# frontpanel1_1.net
KiCad netlist of a schematic drawn in EAGLE
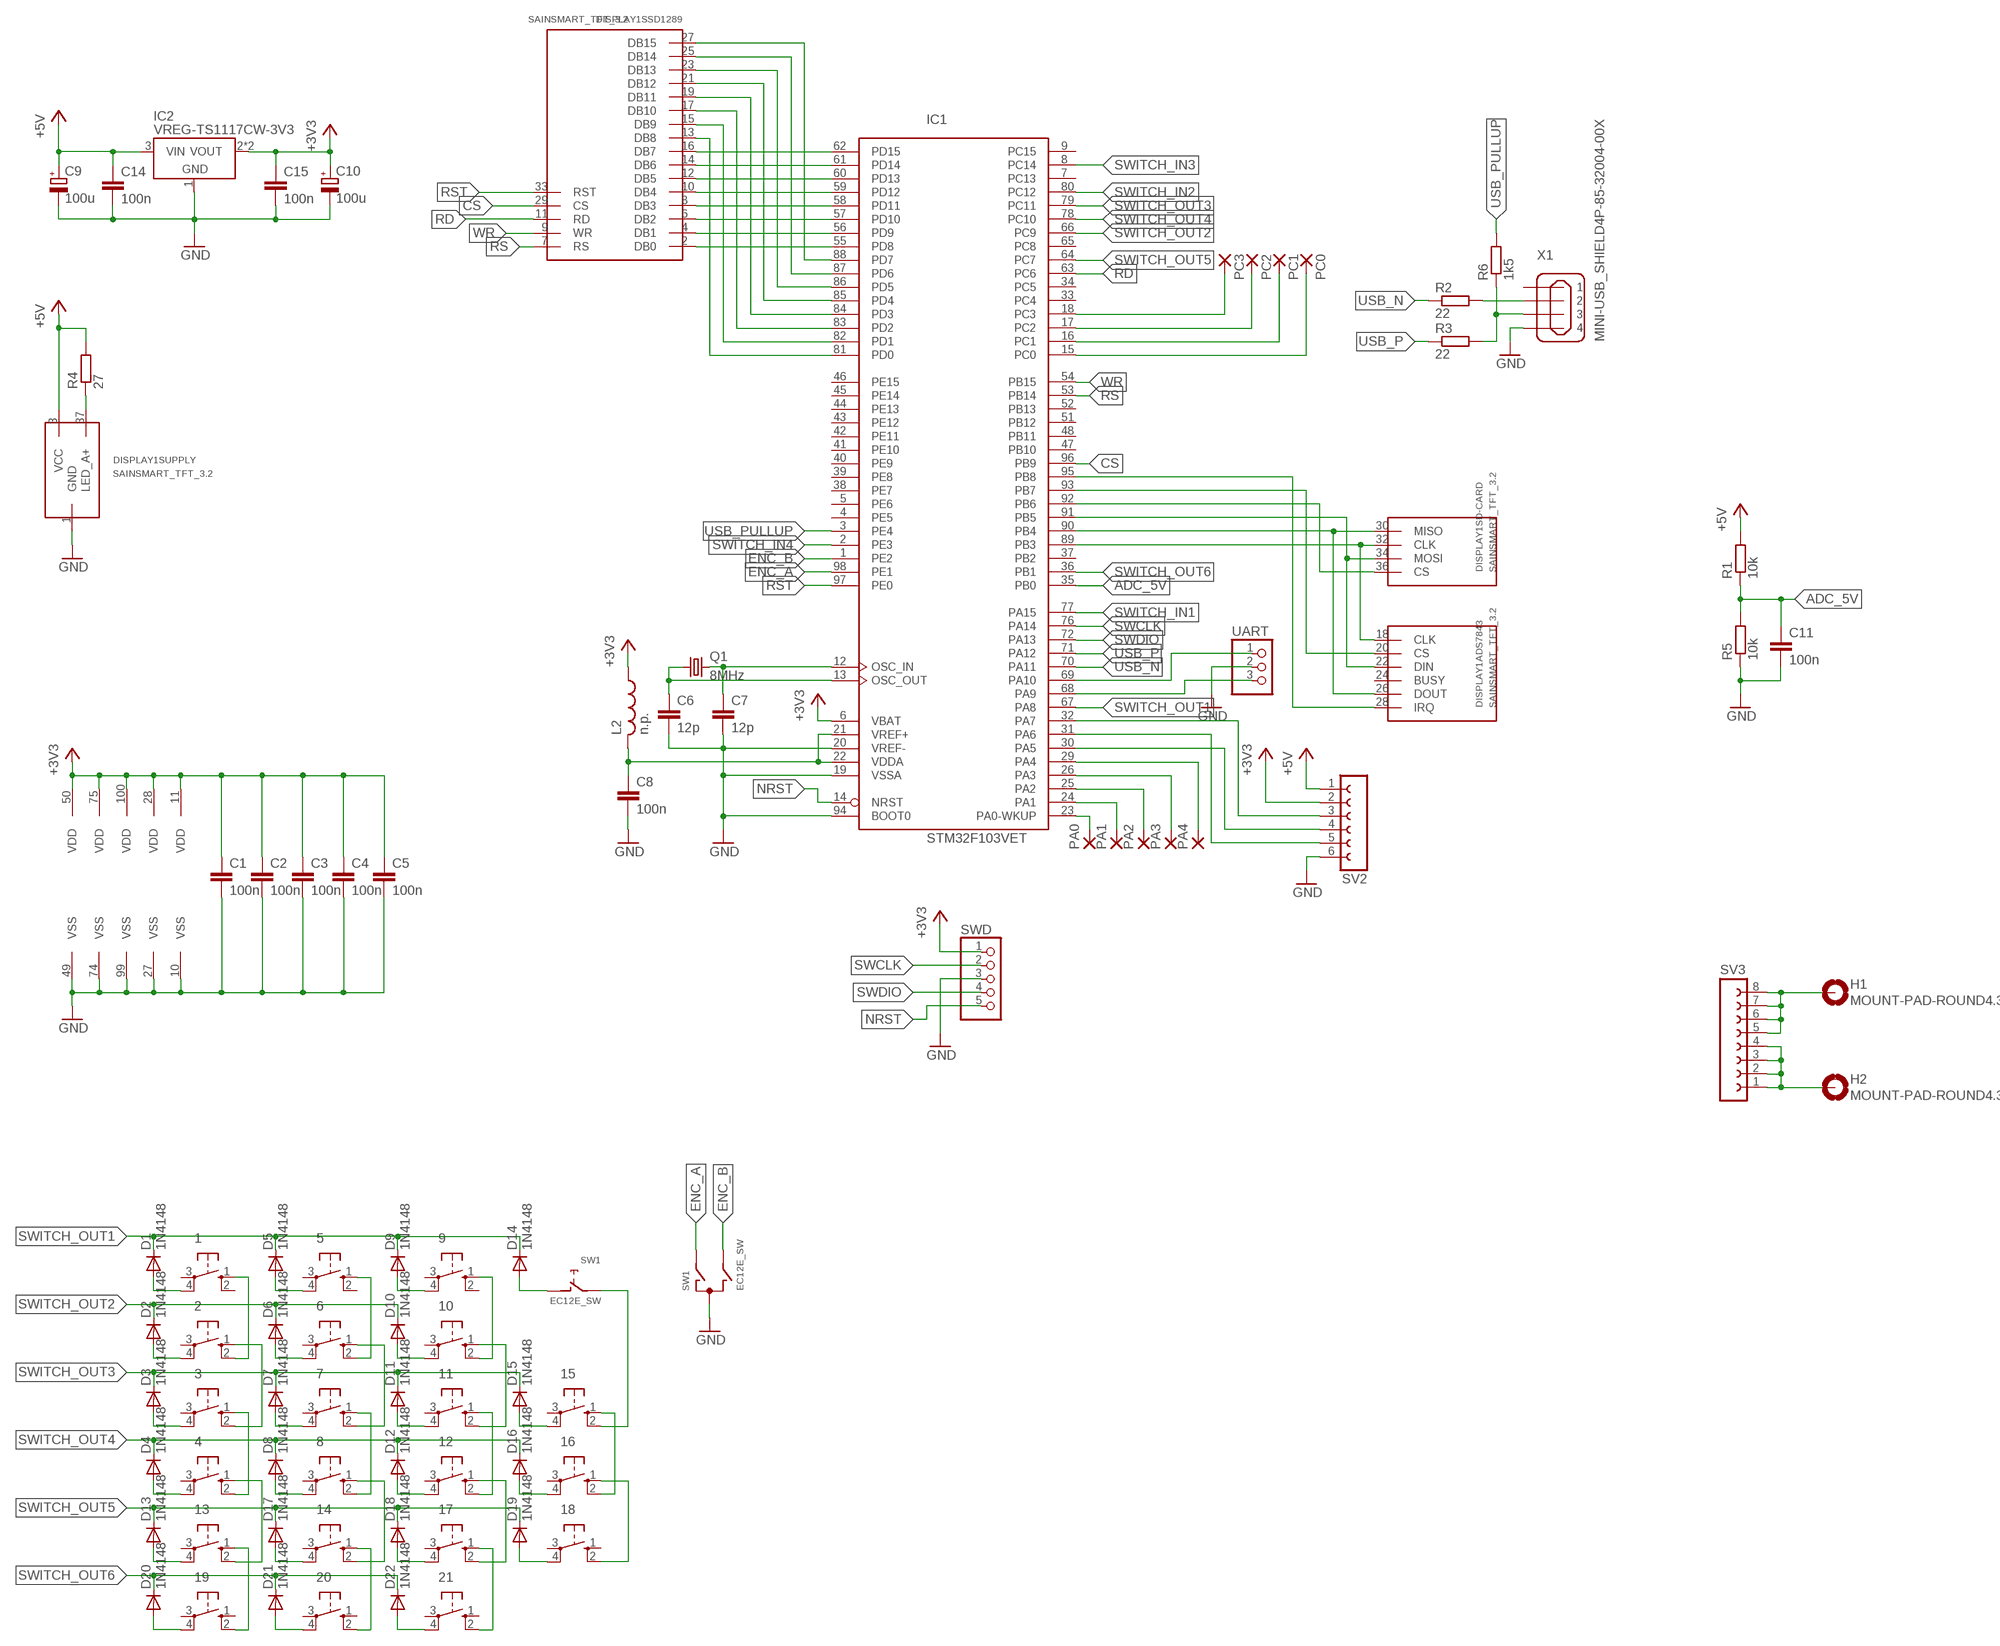
[diagram p0: schematic, sheet 1]

(export (version "E")
  (design (tool "Eeschema 10.0.6"))
  (components
    (comp (ref "1")
      (value "10-XXSMD")
      (footprint "eagle-import:SMD")
      (libsource (lib "eagle-import") (part "10-XXSMD"))
    )
    (comp (ref "2")
      (value "10-XXSMD")
      (footprint "eagle-import:SMD")
      (libsource (lib "eagle-import") (part "10-XXSMD"))
    )
    (comp (ref "3")
      (value "10-XXSMD")
      (footprint "eagle-import:SMD")
      (libsource (lib "eagle-import") (part "10-XXSMD"))
    )
    (comp (ref "4")
      (value "10-XXSMD")
      (footprint "eagle-import:SMD")
      (libsource (lib "eagle-import") (part "10-XXSMD"))
    )
    (comp (ref "5")
      (value "10-XXSMD")
      (footprint "eagle-import:SMD")
      (libsource (lib "eagle-import") (part "10-XXSMD"))
    )
    (comp (ref "6")
      (value "10-XXSMD")
      (footprint "eagle-import:SMD")
      (libsource (lib "eagle-import") (part "10-XXSMD"))
    )
    (comp (ref "7")
      (value "10-XXSMD")
      (footprint "eagle-import:SMD")
      (libsource (lib "eagle-import") (part "10-XXSMD"))
    )
    (comp (ref "8")
      (value "10-XXSMD")
      (footprint "eagle-import:SMD")
      (libsource (lib "eagle-import") (part "10-XXSMD"))
    )
    (comp (ref "9")
      (value "10-XXSMD")
      (footprint "eagle-import:SMD")
      (libsource (lib "eagle-import") (part "10-XXSMD"))
    )
    (comp (ref "10")
      (value "10-XXSMD")
      (footprint "eagle-import:SMD")
      (libsource (lib "eagle-import") (part "10-XXSMD"))
    )
    (comp (ref "11")
      (value "10-XXSMD")
      (footprint "eagle-import:SMD")
      (libsource (lib "eagle-import") (part "10-XXSMD"))
    )
    (comp (ref "12")
      (value "10-XXSMD")
      (footprint "eagle-import:SMD")
      (libsource (lib "eagle-import") (part "10-XXSMD"))
    )
    (comp (ref "13")
      (value "10-XXSMD")
      (footprint "eagle-import:SMD")
      (libsource (lib "eagle-import") (part "10-XXSMD"))
    )
    (comp (ref "14")
      (value "10-XXSMD")
      (footprint "eagle-import:SMD")
      (libsource (lib "eagle-import") (part "10-XXSMD"))
    )
    (comp (ref "15")
      (value "10-XXSMD")
      (footprint "eagle-import:SMD")
      (libsource (lib "eagle-import") (part "10-XXSMD"))
    )
    (comp (ref "16")
      (value "10-XXSMD")
      (footprint "eagle-import:SMD")
      (libsource (lib "eagle-import") (part "10-XXSMD"))
    )
    (comp (ref "17")
      (value "10-XXSMD")
      (footprint "eagle-import:SMD")
      (libsource (lib "eagle-import") (part "10-XXSMD"))
    )
    (comp (ref "18")
      (value "10-XXSMD")
      (footprint "eagle-import:SMD")
      (libsource (lib "eagle-import") (part "10-XXSMD"))
    )
    (comp (ref "19")
      (value "10-XXSMD")
      (footprint "eagle-import:SMD")
      (libsource (lib "eagle-import") (part "10-XXSMD"))
    )
    (comp (ref "20")
      (value "10-XXSMD")
      (footprint "eagle-import:SMD")
      (libsource (lib "eagle-import") (part "10-XXSMD"))
    )
    (comp (ref "21")
      (value "10-XXSMD")
      (footprint "eagle-import:SMD")
      (libsource (lib "eagle-import") (part "10-XXSMD"))
    )
    (comp (ref "C1")
      (value "100n")
      (footprint "eagle-import:C0603K")
      (libsource (lib "eagle-import") (part "C-EUC0603K"))
    )
    (comp (ref "C2")
      (value "100n")
      (footprint "eagle-import:C0603K")
      (libsource (lib "eagle-import") (part "C-EUC0603K"))
    )
    (comp (ref "C3")
      (value "100n")
      (footprint "eagle-import:C0603K")
      (libsource (lib "eagle-import") (part "C-EUC0603K"))
    )
    (comp (ref "C4")
      (value "100n")
      (footprint "eagle-import:C0603K")
      (libsource (lib "eagle-import") (part "C-EUC0603K"))
    )
    (comp (ref "C5")
      (value "100n")
      (footprint "eagle-import:C0603K")
      (libsource (lib "eagle-import") (part "C-EUC0603K"))
    )
    (comp (ref "C6")
      (value "12p")
      (footprint "eagle-import:C0603K")
      (libsource (lib "eagle-import") (part "C-EUC0603K"))
    )
    (comp (ref "C7")
      (value "12p")
      (footprint "eagle-import:C0603K")
      (libsource (lib "eagle-import") (part "C-EUC0603K"))
    )
    (comp (ref "C8")
      (value "100n")
      (footprint "eagle-import:C0603K")
      (libsource (lib "eagle-import") (part "C-EUC0603K"))
    )
    (comp (ref "C9")
      (value "100u")
      (footprint "eagle-import:153CLV-0505")
      (libsource (lib "eagle-import") (part "CPOL-EU153CLV-0505"))
    )
    (comp (ref "C10")
      (value "100u")
      (footprint "eagle-import:153CLV-0505")
      (libsource (lib "eagle-import") (part "CPOL-EU153CLV-0505"))
    )
    (comp (ref "C11")
      (value "100n")
      (footprint "eagle-import:C0603K")
      (libsource (lib "eagle-import") (part "resistormod_C-EUC0603K"))
    )
    (comp (ref "C14")
      (value "100n")
      (footprint "eagle-import:C0603K")
      (libsource (lib "eagle-import") (part "resistormod_C-EUC0603K"))
    )
    (comp (ref "C15")
      (value "100n")
      (footprint "eagle-import:C0603K")
      (libsource (lib "eagle-import") (part "resistormod_C-EUC0603K"))
    )
    (comp (ref "D1")
      (value "1N4148")
      (footprint "eagle-import:SOD323-W")
      (libsource (lib "eagle-import") (part "DIODE-SOD323-W"))
    )
    (comp (ref "D2")
      (value "1N4148")
      (footprint "eagle-import:SOD323-W")
      (libsource (lib "eagle-import") (part "DIODE-SOD323-W"))
    )
    (comp (ref "D3")
      (value "1N4148")
      (footprint "eagle-import:SOD323-W")
      (libsource (lib "eagle-import") (part "DIODE-SOD323-W"))
    )
    (comp (ref "D4")
      (value "1N4148")
      (footprint "eagle-import:SOD323-W")
      (libsource (lib "eagle-import") (part "DIODE-SOD323-W"))
    )
    (comp (ref "D5")
      (value "1N4148")
      (footprint "eagle-import:SOD323-W")
      (libsource (lib "eagle-import") (part "DIODE-SOD323-W"))
    )
    (comp (ref "D6")
      (value "1N4148")
      (footprint "eagle-import:SOD323-W")
      (libsource (lib "eagle-import") (part "DIODE-SOD323-W"))
    )
    (comp (ref "D7")
      (value "1N4148")
      (footprint "eagle-import:SOD323-W")
      (libsource (lib "eagle-import") (part "DIODE-SOD323-W"))
    )
    (comp (ref "D8")
      (value "1N4148")
      (footprint "eagle-import:SOD323-W")
      (libsource (lib "eagle-import") (part "DIODE-SOD323-W"))
    )
    (comp (ref "D9")
      (value "1N4148")
      (footprint "eagle-import:SOD323-W")
      (libsource (lib "eagle-import") (part "DIODE-SOD323-W"))
    )
    (comp (ref "D10")
      (value "1N4148")
      (footprint "eagle-import:SOD323-W")
      (libsource (lib "eagle-import") (part "DIODE-SOD323-W"))
    )
    (comp (ref "D11")
      (value "1N4148")
      (footprint "eagle-import:SOD323-W")
      (libsource (lib "eagle-import") (part "DIODE-SOD323-W"))
    )
    (comp (ref "D12")
      (value "1N4148")
      (footprint "eagle-import:SOD323-W")
      (libsource (lib "eagle-import") (part "DIODE-SOD323-W"))
    )
    (comp (ref "D13")
      (value "1N4148")
      (footprint "eagle-import:SOD323-W")
      (libsource (lib "eagle-import") (part "DIODE-SOD323-W"))
    )
    (comp (ref "D14")
      (value "1N4148")
      (footprint "eagle-import:SOD323-W")
      (libsource (lib "eagle-import") (part "DIODE-SOD323-W"))
    )
    (comp (ref "D15")
      (value "1N4148")
      (footprint "eagle-import:SOD323-W")
      (libsource (lib "eagle-import") (part "DIODE-SOD323-W"))
    )
    (comp (ref "D16")
      (value "1N4148")
      (footprint "eagle-import:SOD323-W")
      (libsource (lib "eagle-import") (part "DIODE-SOD323-W"))
    )
    (comp (ref "D17")
      (value "1N4148")
      (footprint "eagle-import:SOD323-W")
      (libsource (lib "eagle-import") (part "DIODE-SOD323-W"))
    )
    (comp (ref "D18")
      (value "1N4148")
      (footprint "eagle-import:SOD323-W")
      (libsource (lib "eagle-import") (part "DIODE-SOD323-W"))
    )
    (comp (ref "D19")
      (value "1N4148")
      (footprint "eagle-import:SOD323-W")
      (libsource (lib "eagle-import") (part "DIODE-SOD323-W"))
    )
    (comp (ref "D20")
      (value "1N4148")
      (footprint "eagle-import:SOD323-W")
      (libsource (lib "eagle-import") (part "DIODE-SOD323-W"))
    )
    (comp (ref "D21")
      (value "1N4148")
      (footprint "eagle-import:SOD323-W")
      (libsource (lib "eagle-import") (part "DIODE-SOD323-W"))
    )
    (comp (ref "D22")
      (value "1N4148")
      (footprint "eagle-import:SOD323-W")
      (libsource (lib "eagle-import") (part "DIODE-SOD323-W"))
    )
    (comp (ref "DISPLAY1")
      (value "SAINSMART_TFT_3.2")
      (footprint "eagle-import:SAINSMART_TFT_3.2")
      (libsource (lib "eagle-import") (part "SAINSMART_TFT_3.2"))
    )
    (comp (ref "H1")
      (value "MOUNT-PAD-ROUND4.3")
      (footprint "eagle-import:4,3-PAD")
      (libsource (lib "eagle-import") (part "MOUNT-PAD-ROUND4.3"))
    )
    (comp (ref "H2")
      (value "MOUNT-PAD-ROUND4.3")
      (footprint "eagle-import:4,3-PAD")
      (libsource (lib "eagle-import") (part "MOUNT-PAD-ROUND4.3"))
    )
    (comp (ref "IC1")
      (value "STM32F103VET")
      (footprint "eagle-import:LQFP100")
      (libsource (lib "eagle-import") (part "STM32F103VTE"))
    )
    (comp (ref "IC2")
      (value "VREG-TS1117CW-3V3")
      (footprint "eagle-import:SOT223")
      (libsource (lib "eagle-import") (part "VREG-TS1117CW-3V3"))
    )
    (comp (ref "L2")
      (value "n.p.")
      (footprint "eagle-import:R0603")
      (libsource (lib "eagle-import") (part "INDUCTOR0603"))
    )
    (comp (ref "PA0")
      (value "SMD2")
      (footprint "eagle-import:SMD1,27-2,54")
      (libsource (lib "eagle-import") (part "SMD2"))
    )
    (comp (ref "PA1")
      (value "SMD2")
      (footprint "eagle-import:SMD1,27-2,54")
      (libsource (lib "eagle-import") (part "SMD2"))
    )
    (comp (ref "PA2")
      (value "SMD2")
      (footprint "eagle-import:SMD1,27-2,54")
      (libsource (lib "eagle-import") (part "SMD2"))
    )
    (comp (ref "PA3")
      (value "SMD2")
      (footprint "eagle-import:SMD1,27-2,54")
      (libsource (lib "eagle-import") (part "SMD2"))
    )
    (comp (ref "PA4")
      (value "SMD2")
      (footprint "eagle-import:SMD1,27-2,54")
      (libsource (lib "eagle-import") (part "SMD2"))
    )
    (comp (ref "PC0")
      (value "SMD2")
      (footprint "eagle-import:SMD1,27-2,54")
      (libsource (lib "eagle-import") (part "SMD2"))
    )
    (comp (ref "PC1")
      (value "SMD2")
      (footprint "eagle-import:SMD1,27-2,54")
      (libsource (lib "eagle-import") (part "SMD2"))
    )
    (comp (ref "PC2")
      (value "SMD2")
      (footprint "eagle-import:SMD1,27-2,54")
      (libsource (lib "eagle-import") (part "SMD2"))
    )
    (comp (ref "PC3")
      (value "SMD2")
      (footprint "eagle-import:SMD1,27-2,54")
      (libsource (lib "eagle-import") (part "SMD2"))
    )
    (comp (ref "Q1")
      (value "8MHz")
      (footprint "eagle-import:SM49")
      (libsource (lib "eagle-import") (part "CRYSTALSM49"))
    )
    (comp (ref "R1")
      (value "10k")
      (footprint "eagle-import:R0603")
      (libsource (lib "eagle-import") (part "R-EU_R0603"))
    )
    (comp (ref "R2")
      (value "22")
      (footprint "eagle-import:R0603")
      (libsource (lib "eagle-import") (part "R-EU_R0603"))
    )
    (comp (ref "R3")
      (value "22")
      (footprint "eagle-import:R0603")
      (libsource (lib "eagle-import") (part "R-EU_R0603"))
    )
    (comp (ref "R4")
      (value "27")
      (footprint "eagle-import:R1206")
      (libsource (lib "eagle-import") (part "R-EU_R1206"))
    )
    (comp (ref "R5")
      (value "10k")
      (footprint "eagle-import:R0603")
      (libsource (lib "eagle-import") (part "R-EU_R0603"))
    )
    (comp (ref "R6")
      (value "1k5")
      (footprint "eagle-import:R0603")
      (libsource (lib "eagle-import") (part "R-EU_R0603"))
    )
    (comp (ref "SV2")
      (value "FE06-1")
      (footprint "eagle-import:FE06")
      (libsource (lib "eagle-import") (part "FE06-1"))
    )
    (comp (ref "SV3")
      (value "FE08-1")
      (footprint "eagle-import:FE08")
      (libsource (lib "eagle-import") (part "FE08-1"))
    )
    (comp (ref "SW1")
      (value "EC12E_SW")
      (footprint "eagle-import:ALPS_EC12E_SW")
      (fields (field (name "MPN") "EC12E2424407"))
      (libsource (lib "eagle-import") (part "EC12E_SW"))
    )
    (comp (ref "SWD")
      (value "PINHD-1X5")
      (footprint "eagle-import:1X05")
      (libsource (lib "eagle-import") (part "PINHD-1X5"))
    )
    (comp (ref "UART")
      (value "PINHD-1X3")
      (footprint "eagle-import:1X03")
      (libsource (lib "eagle-import") (part "PINHD-1X3"))
    )
    (comp (ref "X1")
      (value "MINI-USB_SHIELD4P-85-32004-00X")
      (footprint "eagle-import:85-32004-00X")
      (libsource (lib "eagle-import") (part "MINI-USB_SHIELD4P-85-32004-00X"))
    )
  )
  (nets
    (net (code "1") (name "+3V3") (class "Default")
      (node (ref "C1") (pin "1") (pinfunction "1_1") (pintype "passive"))
      (node (ref "C10") (pin "+") (pinfunction "+_+") (pintype "passive"))
      (node (ref "C15") (pin "1") (pinfunction "1_1") (pintype "passive"))
      (node (ref "C2") (pin "1") (pinfunction "1_1") (pintype "passive"))
      (node (ref "C3") (pin "1") (pinfunction "1_1") (pintype "passive"))
      (node (ref "C4") (pin "1") (pinfunction "1_1") (pintype "passive"))
      (node (ref "C5") (pin "1") (pinfunction "1_1") (pintype "passive"))
      (node (ref "IC1") (pin "100") (pinfunction "VDD_100") (pintype "power_in"))
      (node (ref "IC1") (pin "11") (pinfunction "VDD_11") (pintype "power_in"))
      (node (ref "IC1") (pin "28") (pinfunction "VDD_28") (pintype "power_in"))
      (node (ref "IC1") (pin "50") (pinfunction "VDD_50") (pintype "power_in"))
      (node (ref "IC1") (pin "6") (pinfunction "VBAT_6") (pintype "power_in"))
      (node (ref "IC1") (pin "75") (pinfunction "VDD_75") (pintype "power_in"))
      (node (ref "IC2") (pin "2") (pinfunction "VOUT_2") (pintype "power_in"))
      (node (ref "IC2") (pin "4") (pinfunction "VOUT_4") (pintype "power_in"))
      (node (ref "L2") (pin "1") (pinfunction "1_1") (pintype "passive"))
      (node (ref "SV2") (pin "2") (pinfunction "2_2") (pintype "passive"))
      (node (ref "SWD") (pin "1") (pinfunction "1_1") (pintype "passive"))
    )
    (net (code "2") (name "+5V") (class "Default")
      (node (ref "C14") (pin "1") (pinfunction "1_1") (pintype "passive"))
      (node (ref "C9") (pin "+") (pinfunction "+_+") (pintype "passive"))
      (node (ref "DISPLAY1") (pin "3") (pinfunction "VCC_3") (pintype "bidirectional"))
      (node (ref "IC2") (pin "3") (pinfunction "VIN_3") (pintype "power_in"))
      (node (ref "R1") (pin "2") (pinfunction "2_2") (pintype "passive"))
      (node (ref "R4") (pin "2") (pinfunction "2_2") (pintype "passive"))
      (node (ref "SV2") (pin "1") (pinfunction "1_1") (pintype "passive"))
    )
    (net (code "3") (name "ADC_5V") (class "Default")
      (node (ref "C11") (pin "1") (pinfunction "1_1") (pintype "passive"))
      (node (ref "IC1") (pin "35") (pinfunction "PB0_35") (pintype "bidirectional"))
      (node (ref "R1") (pin "1") (pinfunction "1_1") (pintype "passive"))
      (node (ref "R5") (pin "2") (pinfunction "2_2") (pintype "passive"))
    )
    (net (code "4") (name "CS") (class "Default")
      (node (ref "DISPLAY1") (pin "29") (pinfunction "CS_29") (pintype "bidirectional"))
      (node (ref "IC1") (pin "96") (pinfunction "PB9_96") (pintype "bidirectional"))
    )
    (net (code "5") (name "ENC_A") (class "Default")
      (node (ref "IC1") (pin "98") (pinfunction "PE1_98") (pintype "bidirectional"))
      (node (ref "SW1") (pin "A") (pinfunction "A_A") (pintype "passive"))
    )
    (net (code "6") (name "ENC_B") (class "Default")
      (node (ref "IC1") (pin "1") (pinfunction "PE2_1") (pintype "bidirectional"))
      (node (ref "SW1") (pin "B") (pinfunction "B_B") (pintype "passive"))
    )
    (net (code "7") (name "GND") (class "Default")
      (node (ref "C1") (pin "2") (pinfunction "2_2") (pintype "passive"))
      (node (ref "C10") (pin "-") (pinfunction "-_-") (pintype "passive"))
      (node (ref "C11") (pin "2") (pinfunction "2_2") (pintype "passive"))
      (node (ref "C14") (pin "2") (pinfunction "2_2") (pintype "passive"))
      (node (ref "C15") (pin "2") (pinfunction "2_2") (pintype "passive"))
      (node (ref "C2") (pin "2") (pinfunction "2_2") (pintype "passive"))
      (node (ref "C3") (pin "2") (pinfunction "2_2") (pintype "passive"))
      (node (ref "C4") (pin "2") (pinfunction "2_2") (pintype "passive"))
      (node (ref "C5") (pin "2") (pinfunction "2_2") (pintype "passive"))
      (node (ref "C6") (pin "2") (pinfunction "2_2") (pintype "passive"))
      (node (ref "C7") (pin "2") (pinfunction "2_2") (pintype "passive"))
      (node (ref "C8") (pin "2") (pinfunction "2_2") (pintype "passive"))
      (node (ref "C9") (pin "-") (pinfunction "-_-") (pintype "passive"))
      (node (ref "DISPLAY1") (pin "1") (pinfunction "GND_1") (pintype "bidirectional"))
      (node (ref "IC1") (pin "10") (pinfunction "VSS_10") (pintype "power_in"))
      (node (ref "IC1") (pin "19") (pinfunction "VSSA_19") (pintype "power_in"))
      (node (ref "IC1") (pin "20") (pinfunction "VREF-_20") (pintype "power_in"))
      (node (ref "IC1") (pin "27") (pinfunction "VSS_27") (pintype "power_in"))
      (node (ref "IC1") (pin "49") (pinfunction "VSS_49") (pintype "power_in"))
      (node (ref "IC1") (pin "74") (pinfunction "VSS_74") (pintype "power_in"))
      (node (ref "IC1") (pin "94") (pinfunction "BOOT0_94") (pintype "input"))
      (node (ref "IC1") (pin "99") (pinfunction "VSS_99") (pintype "power_in"))
      (node (ref "IC2") (pin "1") (pinfunction "GND_1") (pintype "power_in"))
      (node (ref "R5") (pin "1") (pinfunction "1_1") (pintype "passive"))
      (node (ref "SV2") (pin "6") (pinfunction "6_6") (pintype "passive"))
      (node (ref "SW1") (pin "C") (pinfunction "C_C") (pintype "passive"))
      (node (ref "SWD") (pin "3") (pinfunction "3_3") (pintype "passive"))
      (node (ref "UART") (pin "2") (pinfunction "2_2") (pintype "passive"))
      (node (ref "X1") (pin "4") (pinfunction "4_4") (pintype "passive"))
    )
    (net (code "8") (name "NRST") (class "Default")
      (node (ref "IC1") (pin "14") (pinfunction "NRST_14") (pintype "bidirectional"))
      (node (ref "SWD") (pin "5") (pinfunction "5_5") (pintype "passive"))
    )
    (net (code "9") (name "Net-(1-P1)") (class "Default")
      (node (ref "1") (pin "4") (pinfunction "P1_4") (pintype "passive"))
      (node (ref "D1") (pin "A") (pinfunction "A_A") (pintype "passive"))
    )
    (net (code "10") (name "Net-(1-S)") (class "Default")
      (node (ref "1") (pin "1") (pinfunction "S_1") (pintype "passive"))
      (node (ref "2") (pin "2") (pinfunction "S1_2") (pintype "passive"))
    )
    (net (code "11") (name "Net-(2-P1)") (class "Default")
      (node (ref "2") (pin "4") (pinfunction "P1_4") (pintype "passive"))
      (node (ref "D2") (pin "A") (pinfunction "A_A") (pintype "passive"))
    )
    (net (code "12") (name "Net-(2-S)") (class "Default")
      (node (ref "2") (pin "1") (pinfunction "S_1") (pintype "passive"))
      (node (ref "3") (pin "2") (pinfunction "S1_2") (pintype "passive"))
    )
    (net (code "13") (name "Net-(3-P1)") (class "Default")
      (node (ref "3") (pin "4") (pinfunction "P1_4") (pintype "passive"))
      (node (ref "D3") (pin "A") (pinfunction "A_A") (pintype "passive"))
    )
    (net (code "14") (name "Net-(4-P1)") (class "Default")
      (node (ref "4") (pin "4") (pinfunction "P1_4") (pintype "passive"))
      (node (ref "D4") (pin "A") (pinfunction "A_A") (pintype "passive"))
    )
    (net (code "15") (name "Net-(5-P1)") (class "Default")
      (node (ref "5") (pin "4") (pinfunction "P1_4") (pintype "passive"))
      (node (ref "D5") (pin "A") (pinfunction "A_A") (pintype "passive"))
    )
    (net (code "16") (name "Net-(5-S)") (class "Default")
      (node (ref "5") (pin "1") (pinfunction "S_1") (pintype "passive"))
      (node (ref "6") (pin "2") (pinfunction "S1_2") (pintype "passive"))
    )
    (net (code "17") (name "Net-(6-P1)") (class "Default")
      (node (ref "6") (pin "4") (pinfunction "P1_4") (pintype "passive"))
      (node (ref "D6") (pin "A") (pinfunction "A_A") (pintype "passive"))
    )
    (net (code "18") (name "Net-(6-S)") (class "Default")
      (node (ref "6") (pin "1") (pinfunction "S_1") (pintype "passive"))
      (node (ref "7") (pin "2") (pinfunction "S1_2") (pintype "passive"))
    )
    (net (code "19") (name "Net-(7-P1)") (class "Default")
      (node (ref "7") (pin "4") (pinfunction "P1_4") (pintype "passive"))
      (node (ref "D7") (pin "A") (pinfunction "A_A") (pintype "passive"))
    )
    (net (code "20") (name "Net-(8-P1)") (class "Default")
      (node (ref "8") (pin "4") (pinfunction "P1_4") (pintype "passive"))
      (node (ref "D8") (pin "A") (pinfunction "A_A") (pintype "passive"))
    )
    (net (code "21") (name "Net-(9-P1)") (class "Default")
      (node (ref "9") (pin "4") (pinfunction "P1_4") (pintype "passive"))
      (node (ref "D9") (pin "A") (pinfunction "A_A") (pintype "passive"))
    )
    (net (code "22") (name "Net-(10-P1)") (class "Default")
      (node (ref "10") (pin "4") (pinfunction "P1_4") (pintype "passive"))
      (node (ref "D10") (pin "A") (pinfunction "A_A") (pintype "passive"))
    )
    (net (code "23") (name "Net-(10-S)") (class "Default")
      (node (ref "10") (pin "1") (pinfunction "S_1") (pintype "passive"))
      (node (ref "11") (pin "2") (pinfunction "S1_2") (pintype "passive"))
    )
    (net (code "24") (name "Net-(10-S1)") (class "Default")
      (node (ref "10") (pin "2") (pinfunction "S1_2") (pintype "passive"))
      (node (ref "9") (pin "1") (pinfunction "S_1") (pintype "passive"))
    )
    (net (code "25") (name "Net-(11-P1)") (class "Default")
      (node (ref "11") (pin "4") (pinfunction "P1_4") (pintype "passive"))
      (node (ref "D11") (pin "A") (pinfunction "A_A") (pintype "passive"))
    )
    (net (code "26") (name "Net-(11-S)") (class "Default")
      (node (ref "11") (pin "1") (pinfunction "S_1") (pintype "passive"))
      (node (ref "12") (pin "2") (pinfunction "S1_2") (pintype "passive"))
    )
    (net (code "27") (name "Net-(12-P1)") (class "Default")
      (node (ref "12") (pin "4") (pinfunction "P1_4") (pintype "passive"))
      (node (ref "D12") (pin "A") (pinfunction "A_A") (pintype "passive"))
    )
    (net (code "28") (name "Net-(13-P1)") (class "Default")
      (node (ref "13") (pin "4") (pinfunction "P1_4") (pintype "passive"))
      (node (ref "D13") (pin "A") (pinfunction "A_A") (pintype "passive"))
    )
    (net (code "29") (name "Net-(13-S)") (class "Default")
      (node (ref "13") (pin "1") (pinfunction "S_1") (pintype "passive"))
      (node (ref "19") (pin "2") (pinfunction "S1_2") (pintype "passive"))
    )
    (net (code "30") (name "Net-(13-S1)") (class "Default")
      (node (ref "13") (pin "2") (pinfunction "S1_2") (pintype "passive"))
      (node (ref "4") (pin "1") (pinfunction "S_1") (pintype "passive"))
    )
    (net (code "31") (name "Net-(14-P1)") (class "Default")
      (node (ref "14") (pin "4") (pinfunction "P1_4") (pintype "passive"))
      (node (ref "D17") (pin "A") (pinfunction "A_A") (pintype "passive"))
    )
    (net (code "32") (name "Net-(14-S)") (class "Default")
      (node (ref "14") (pin "1") (pinfunction "S_1") (pintype "passive"))
      (node (ref "20") (pin "2") (pinfunction "S1_2") (pintype "passive"))
    )
    (net (code "33") (name "Net-(14-S1)") (class "Default")
      (node (ref "14") (pin "2") (pinfunction "S1_2") (pintype "passive"))
      (node (ref "8") (pin "1") (pinfunction "S_1") (pintype "passive"))
    )
    (net (code "34") (name "Net-(15-P1)") (class "Default")
      (node (ref "15") (pin "4") (pinfunction "P1_4") (pintype "passive"))
      (node (ref "D15") (pin "A") (pinfunction "A_A") (pintype "passive"))
    )
    (net (code "35") (name "Net-(15-S)") (class "Default")
      (node (ref "15") (pin "1") (pinfunction "S_1") (pintype "passive"))
      (node (ref "16") (pin "2") (pinfunction "S1_2") (pintype "passive"))
    )
    (net (code "36") (name "Net-(15-S1)") (class "Default")
      (node (ref "15") (pin "2") (pinfunction "S1_2") (pintype "passive"))
      (node (ref "SW1") (pin "E") (pinfunction "2_E") (pintype "passive"))
    )
    (net (code "37") (name "Net-(16-P1)") (class "Default")
      (node (ref "16") (pin "4") (pinfunction "P1_4") (pintype "passive"))
      (node (ref "D16") (pin "A") (pinfunction "A_A") (pintype "passive"))
    )
    (net (code "38") (name "Net-(17-P1)") (class "Default")
      (node (ref "17") (pin "4") (pinfunction "P1_4") (pintype "passive"))
      (node (ref "D18") (pin "A") (pinfunction "A_A") (pintype "passive"))
    )
    (net (code "39") (name "Net-(17-S)") (class "Default")
      (node (ref "17") (pin "1") (pinfunction "S_1") (pintype "passive"))
      (node (ref "21") (pin "2") (pinfunction "S1_2") (pintype "passive"))
    )
    (net (code "40") (name "Net-(18-P1)") (class "Default")
      (node (ref "18") (pin "4") (pinfunction "P1_4") (pintype "passive"))
      (node (ref "D19") (pin "A") (pinfunction "A_A") (pintype "passive"))
    )
    (net (code "41") (name "Net-(19-P1)") (class "Default")
      (node (ref "19") (pin "4") (pinfunction "P1_4") (pintype "passive"))
      (node (ref "D20") (pin "A") (pinfunction "A_A") (pintype "passive"))
    )
    (net (code "42") (name "Net-(20-P1)") (class "Default")
      (node (ref "20") (pin "4") (pinfunction "P1_4") (pintype "passive"))
      (node (ref "D21") (pin "A") (pinfunction "A_A") (pintype "passive"))
    )
    (net (code "43") (name "Net-(21-P1)") (class "Default")
      (node (ref "21") (pin "4") (pinfunction "P1_4") (pintype "passive"))
      (node (ref "D22") (pin "A") (pinfunction "A_A") (pintype "passive"))
    )
    (net (code "44") (name "Net-(DISPLAY1A-CLK)") (class "Default")
      (node (ref "DISPLAY1") (pin "18") (pinfunction "CLK_18") (pintype "bidirectional"))
      (node (ref "DISPLAY1") (pin "32") (pinfunction "CLK_32") (pintype "bidirectional"))
      (node (ref "IC1") (pin "89") (pinfunction "PB3_89") (pintype "bidirectional"))
    )
    (net (code "45") (name "Net-(DISPLAY1A-CS)") (class "Default")
      (node (ref "DISPLAY1") (pin "20") (pinfunction "CS_20") (pintype "bidirectional"))
      (node (ref "IC1") (pin "93") (pinfunction "PB7_93") (pintype "bidirectional"))
    )
    (net (code "46") (name "Net-(DISPLAY1A-DIN)") (class "Default")
      (node (ref "DISPLAY1") (pin "22") (pinfunction "DIN_22") (pintype "bidirectional"))
      (node (ref "DISPLAY1") (pin "34") (pinfunction "MOSI_34") (pintype "bidirectional"))
      (node (ref "IC1") (pin "91") (pinfunction "PB5_91") (pintype "bidirectional"))
    )
    (net (code "47") (name "Net-(DISPLAY1A-DOUT)") (class "Default")
      (node (ref "DISPLAY1") (pin "26") (pinfunction "DOUT_26") (pintype "bidirectional"))
      (node (ref "DISPLAY1") (pin "30") (pinfunction "MISO_30") (pintype "bidirectional"))
      (node (ref "IC1") (pin "90") (pinfunction "PB4_90") (pintype "bidirectional"))
    )
    (net (code "48") (name "Net-(DISPLAY1A-IRQ)") (class "Default")
      (node (ref "DISPLAY1") (pin "28") (pinfunction "IRQ_28") (pintype "bidirectional"))
      (node (ref "IC1") (pin "95") (pinfunction "PB8_95") (pintype "bidirectional"))
    )
    (net (code "49") (name "Net-(DISPLAY1B-CS)") (class "Default")
      (node (ref "DISPLAY1") (pin "36") (pinfunction "CS_36") (pintype "bidirectional"))
      (node (ref "IC1") (pin "92") (pinfunction "PB6_92") (pintype "bidirectional"))
    )
    (net (code "50") (name "Net-(DISPLAY1C-DB0)") (class "Default")
      (node (ref "DISPLAY1") (pin "2") (pinfunction "DB0_2") (pintype "bidirectional"))
      (node (ref "IC1") (pin "55") (pinfunction "PD8_55") (pintype "bidirectional"))
    )
    (net (code "51") (name "Net-(DISPLAY1C-DB1)") (class "Default")
      (node (ref "DISPLAY1") (pin "4") (pinfunction "DB1_4") (pintype "bidirectional"))
      (node (ref "IC1") (pin "56") (pinfunction "PD9_56") (pintype "bidirectional"))
    )
    (net (code "52") (name "Net-(DISPLAY1C-DB2)") (class "Default")
      (node (ref "DISPLAY1") (pin "6") (pinfunction "DB2_6") (pintype "bidirectional"))
      (node (ref "IC1") (pin "57") (pinfunction "PD10_57") (pintype "bidirectional"))
    )
    (net (code "53") (name "Net-(DISPLAY1C-DB3)") (class "Default")
      (node (ref "DISPLAY1") (pin "8") (pinfunction "DB3_8") (pintype "bidirectional"))
      (node (ref "IC1") (pin "58") (pinfunction "PD11_58") (pintype "bidirectional"))
    )
    (net (code "54") (name "Net-(DISPLAY1C-DB4)") (class "Default")
      (node (ref "DISPLAY1") (pin "10") (pinfunction "DB4_10") (pintype "bidirectional"))
      (node (ref "IC1") (pin "59") (pinfunction "PD12_59") (pintype "bidirectional"))
    )
    (net (code "55") (name "Net-(DISPLAY1C-DB5)") (class "Default")
      (node (ref "DISPLAY1") (pin "12") (pinfunction "DB5_12") (pintype "bidirectional"))
      (node (ref "IC1") (pin "60") (pinfunction "PD13_60") (pintype "bidirectional"))
    )
    (net (code "56") (name "Net-(DISPLAY1C-DB6)") (class "Default")
      (node (ref "DISPLAY1") (pin "14") (pinfunction "DB6_14") (pintype "bidirectional"))
      (node (ref "IC1") (pin "61") (pinfunction "PD14_61") (pintype "bidirectional"))
    )
    (net (code "57") (name "Net-(DISPLAY1C-DB7)") (class "Default")
      (node (ref "DISPLAY1") (pin "16") (pinfunction "DB7_16") (pintype "bidirectional"))
      (node (ref "IC1") (pin "62") (pinfunction "PD15_62") (pintype "bidirectional"))
    )
    (net (code "58") (name "Net-(DISPLAY1C-DB8)") (class "Default")
      (node (ref "DISPLAY1") (pin "13") (pinfunction "DB8_13") (pintype "bidirectional"))
      (node (ref "IC1") (pin "81") (pinfunction "PD0_81") (pintype "bidirectional"))
    )
    (net (code "59") (name "Net-(DISPLAY1C-DB9)") (class "Default")
      (node (ref "DISPLAY1") (pin "15") (pinfunction "DB9_15") (pintype "bidirectional"))
      (node (ref "IC1") (pin "82") (pinfunction "PD1_82") (pintype "bidirectional"))
    )
    (net (code "60") (name "Net-(DISPLAY1C-DB10)") (class "Default")
      (node (ref "DISPLAY1") (pin "17") (pinfunction "DB10_17") (pintype "bidirectional"))
      (node (ref "IC1") (pin "83") (pinfunction "PD2_83") (pintype "bidirectional"))
    )
    (net (code "61") (name "Net-(DISPLAY1C-DB11)") (class "Default")
      (node (ref "DISPLAY1") (pin "19") (pinfunction "DB11_19") (pintype "bidirectional"))
      (node (ref "IC1") (pin "84") (pinfunction "PD3_84") (pintype "bidirectional"))
    )
    (net (code "62") (name "Net-(DISPLAY1C-DB12)") (class "Default")
      (node (ref "DISPLAY1") (pin "21") (pinfunction "DB12_21") (pintype "bidirectional"))
      (node (ref "IC1") (pin "85") (pinfunction "PD4_85") (pintype "bidirectional"))
    )
    (net (code "63") (name "Net-(DISPLAY1C-DB13)") (class "Default")
      (node (ref "DISPLAY1") (pin "23") (pinfunction "DB13_23") (pintype "bidirectional"))
      (node (ref "IC1") (pin "86") (pinfunction "PD5_86") (pintype "bidirectional"))
    )
    (net (code "64") (name "Net-(DISPLAY1C-DB14)") (class "Default")
      (node (ref "DISPLAY1") (pin "25") (pinfunction "DB14_25") (pintype "bidirectional"))
      (node (ref "IC1") (pin "87") (pinfunction "PD6_87") (pintype "bidirectional"))
    )
    (net (code "65") (name "Net-(DISPLAY1C-DB15)") (class "Default")
      (node (ref "DISPLAY1") (pin "27") (pinfunction "DB15_27") (pintype "bidirectional"))
      (node (ref "IC1") (pin "88") (pinfunction "PD7_88") (pintype "bidirectional"))
    )
    (net (code "66") (name "Net-(DISPLAY1D-LED_A+)") (class "Default")
      (node (ref "DISPLAY1") (pin "37") (pinfunction "LED_A+_37") (pintype "bidirectional"))
      (node (ref "R4") (pin "1") (pinfunction "1_1") (pintype "passive"))
    )
    (net (code "67") (name "Net-(H1-MOUNT)") (class "Default")
      (node (ref "H1") (pin "B4,3") (pinfunction "MOUNT_B4,3") (pintype "passive"))
      (node (ref "SV3") (pin "5") (pinfunction "5_5") (pintype "passive"))
      (node (ref "SV3") (pin "6") (pinfunction "6_6") (pintype "passive"))
      (node (ref "SV3") (pin "7") (pinfunction "7_7") (pintype "passive"))
      (node (ref "SV3") (pin "8") (pinfunction "8_8") (pintype "passive"))
    )
    (net (code "68") (name "Net-(H2-MOUNT)") (class "Default")
      (node (ref "H2") (pin "B4,3") (pinfunction "MOUNT_B4,3") (pintype "passive"))
      (node (ref "SV3") (pin "1") (pinfunction "1_1") (pintype "passive"))
      (node (ref "SV3") (pin "2") (pinfunction "2_2") (pintype "passive"))
      (node (ref "SV3") (pin "3") (pinfunction "3_3") (pintype "passive"))
      (node (ref "SV3") (pin "4") (pinfunction "4_4") (pintype "passive"))
    )
    (net (code "69") (name "Net-(IC1A-OSC_IN)") (class "Default")
      (node (ref "C7") (pin "1") (pinfunction "1_1") (pintype "passive"))
      (node (ref "IC1") (pin "12") (pinfunction "OSC_IN_12") (pintype "bidirectional"))
      (node (ref "Q1") (pin "2") (pinfunction "2_2") (pintype "passive"))
    )
    (net (code "70") (name "Net-(IC1A-OSC_OUT)") (class "Default")
      (node (ref "C6") (pin "1") (pinfunction "1_1") (pintype "passive"))
      (node (ref "IC1") (pin "13") (pinfunction "OSC_OUT_13") (pintype "bidirectional"))
      (node (ref "Q1") (pin "1") (pinfunction "1_1") (pintype "passive"))
    )
    (net (code "71") (name "Net-(IC1A-PA0-WKUP)") (class "Default")
      (node (ref "IC1") (pin "23") (pinfunction "PA0-WKUP_23") (pintype "bidirectional"))
      (node (ref "PA0") (pin "1") (pinfunction "P_1") (pintype "passive"))
    )
    (net (code "72") (name "Net-(IC1A-PA1)") (class "Default")
      (node (ref "IC1") (pin "24") (pinfunction "PA1_24") (pintype "bidirectional"))
      (node (ref "PA1") (pin "1") (pinfunction "P_1") (pintype "passive"))
    )
    (net (code "73") (name "Net-(IC1A-PA2)") (class "Default")
      (node (ref "IC1") (pin "25") (pinfunction "PA2_25") (pintype "bidirectional"))
      (node (ref "PA2") (pin "1") (pinfunction "P_1") (pintype "passive"))
    )
    (net (code "74") (name "Net-(IC1A-PA3)") (class "Default")
      (node (ref "IC1") (pin "26") (pinfunction "PA3_26") (pintype "bidirectional"))
      (node (ref "PA3") (pin "1") (pinfunction "P_1") (pintype "passive"))
    )
    (net (code "75") (name "Net-(IC1A-PA4)") (class "Default")
      (node (ref "IC1") (pin "29") (pinfunction "PA4_29") (pintype "bidirectional"))
      (node (ref "PA4") (pin "1") (pinfunction "P_1") (pintype "passive"))
    )
    (net (code "76") (name "Net-(IC1A-PA5)") (class "Default")
      (node (ref "IC1") (pin "30") (pinfunction "PA5_30") (pintype "bidirectional"))
      (node (ref "SV2") (pin "4") (pinfunction "4_4") (pintype "passive"))
    )
    (net (code "77") (name "Net-(IC1A-PA6)") (class "Default")
      (node (ref "IC1") (pin "31") (pinfunction "PA6_31") (pintype "bidirectional"))
      (node (ref "SV2") (pin "5") (pinfunction "5_5") (pintype "passive"))
    )
    (net (code "78") (name "Net-(IC1A-PA7)") (class "Default")
      (node (ref "IC1") (pin "32") (pinfunction "PA7_32") (pintype "bidirectional"))
      (node (ref "SV2") (pin "3") (pinfunction "3_3") (pintype "passive"))
    )
    (net (code "79") (name "Net-(IC1A-PA9)") (class "Default")
      (node (ref "IC1") (pin "68") (pinfunction "PA9_68") (pintype "bidirectional"))
      (node (ref "UART") (pin "3") (pinfunction "3_3") (pintype "passive"))
    )
    (net (code "80") (name "Net-(IC1A-PA10)") (class "Default")
      (node (ref "IC1") (pin "69") (pinfunction "PA10_69") (pintype "bidirectional"))
      (node (ref "UART") (pin "1") (pinfunction "1_1") (pintype "passive"))
    )
    (net (code "81") (name "Net-(IC1A-PC0)") (class "Default")
      (node (ref "IC1") (pin "15") (pinfunction "PC0_15") (pintype "bidirectional"))
      (node (ref "PC0") (pin "1") (pinfunction "P_1") (pintype "passive"))
    )
    (net (code "82") (name "Net-(IC1A-PC1)") (class "Default")
      (node (ref "IC1") (pin "16") (pinfunction "PC1_16") (pintype "bidirectional"))
      (node (ref "PC1") (pin "1") (pinfunction "P_1") (pintype "passive"))
    )
    (net (code "83") (name "Net-(IC1A-PC2)") (class "Default")
      (node (ref "IC1") (pin "17") (pinfunction "PC2_17") (pintype "bidirectional"))
      (node (ref "PC2") (pin "1") (pinfunction "P_1") (pintype "passive"))
    )
    (net (code "84") (name "Net-(IC1A-PC3)") (class "Default")
      (node (ref "IC1") (pin "18") (pinfunction "PC3_18") (pintype "bidirectional"))
      (node (ref "PC3") (pin "1") (pinfunction "P_1") (pintype "passive"))
    )
    (net (code "85") (name "Net-(IC1A-VDDA)") (class "Default")
      (node (ref "C8") (pin "1") (pinfunction "1_1") (pintype "passive"))
      (node (ref "IC1") (pin "21") (pinfunction "VREF+_21") (pintype "power_in"))
      (node (ref "IC1") (pin "22") (pinfunction "VDDA_22") (pintype "power_in"))
      (node (ref "L2") (pin "2") (pinfunction "2_2") (pintype "passive"))
    )
    (net (code "86") (name "Net-(R2-Pad2)") (class "Default")
      (node (ref "R2") (pin "2") (pinfunction "2_2") (pintype "passive"))
      (node (ref "X1") (pin "2") (pinfunction "2_2") (pintype "passive"))
    )
    (net (code "87") (name "Net-(R3-Pad2)") (class "Default")
      (node (ref "R3") (pin "2") (pinfunction "2_2") (pintype "passive"))
      (node (ref "R6") (pin "1") (pinfunction "1_1") (pintype "passive"))
      (node (ref "X1") (pin "3") (pinfunction "3_3") (pintype "passive"))
    )
    (net (code "88") (name "Net-(SW1B-1)") (class "Default")
      (node (ref "D14") (pin "A") (pinfunction "A_A") (pintype "passive"))
      (node (ref "SW1") (pin "D") (pinfunction "1_D") (pintype "passive"))
    )
    (net (code "89") (name "RD") (class "Default")
      (node (ref "DISPLAY1") (pin "11") (pinfunction "RD_11") (pintype "bidirectional"))
      (node (ref "IC1") (pin "63") (pinfunction "PC6_63") (pintype "bidirectional"))
    )
    (net (code "90") (name "RS") (class "Default")
      (node (ref "DISPLAY1") (pin "7") (pinfunction "RS_7") (pintype "bidirectional"))
      (node (ref "IC1") (pin "53") (pinfunction "PB14_53") (pintype "bidirectional"))
    )
    (net (code "91") (name "RST") (class "Default")
      (node (ref "DISPLAY1") (pin "33") (pinfunction "RST_33") (pintype "bidirectional"))
      (node (ref "IC1") (pin "97") (pinfunction "PE0_97") (pintype "bidirectional"))
    )
    (net (code "92") (name "SWCLK") (class "Default")
      (node (ref "IC1") (pin "76") (pinfunction "PA14_76") (pintype "bidirectional"))
      (node (ref "SWD") (pin "2") (pinfunction "2_2") (pintype "passive"))
    )
    (net (code "93") (name "SWDIO") (class "Default")
      (node (ref "IC1") (pin "72") (pinfunction "PA13_72") (pintype "bidirectional"))
      (node (ref "SWD") (pin "4") (pinfunction "4_4") (pintype "passive"))
    )
    (net (code "94") (name "SWITCH_IN1") (class "Default")
      (node (ref "3") (pin "1") (pinfunction "S_1") (pintype "passive"))
      (node (ref "4") (pin "2") (pinfunction "S1_2") (pintype "passive"))
      (node (ref "IC1") (pin "77") (pinfunction "PA15_77") (pintype "bidirectional"))
    )
    (net (code "95") (name "SWITCH_IN2") (class "Default")
      (node (ref "7") (pin "1") (pinfunction "S_1") (pintype "passive"))
      (node (ref "8") (pin "2") (pinfunction "S1_2") (pintype "passive"))
      (node (ref "IC1") (pin "80") (pinfunction "PC12_80") (pintype "bidirectional"))
    )
    (net (code "96") (name "SWITCH_IN3") (class "Default")
      (node (ref "12") (pin "1") (pinfunction "S_1") (pintype "passive"))
      (node (ref "17") (pin "2") (pinfunction "S1_2") (pintype "passive"))
      (node (ref "IC1") (pin "8") (pinfunction "PC14_8") (pintype "bidirectional"))
    )
    (net (code "97") (name "SWITCH_IN4") (class "Default")
      (node (ref "16") (pin "1") (pinfunction "S_1") (pintype "passive"))
      (node (ref "18") (pin "2") (pinfunction "S1_2") (pintype "passive"))
      (node (ref "IC1") (pin "2") (pinfunction "PE3_2") (pintype "bidirectional"))
    )
    (net (code "98") (name "SWITCH_OUT1") (class "Default")
      (node (ref "D1") (pin "C") (pinfunction "C_C") (pintype "passive"))
      (node (ref "D14") (pin "C") (pinfunction "C_C") (pintype "passive"))
      (node (ref "D5") (pin "C") (pinfunction "C_C") (pintype "passive"))
      (node (ref "D9") (pin "C") (pinfunction "C_C") (pintype "passive"))
      (node (ref "IC1") (pin "67") (pinfunction "PA8_67") (pintype "bidirectional"))
    )
    (net (code "99") (name "SWITCH_OUT2") (class "Default")
      (node (ref "D10") (pin "C") (pinfunction "C_C") (pintype "passive"))
      (node (ref "D2") (pin "C") (pinfunction "C_C") (pintype "passive"))
      (node (ref "D6") (pin "C") (pinfunction "C_C") (pintype "passive"))
      (node (ref "IC1") (pin "66") (pinfunction "PC9_66") (pintype "bidirectional"))
    )
    (net (code "100") (name "SWITCH_OUT3") (class "Default")
      (node (ref "D11") (pin "C") (pinfunction "C_C") (pintype "passive"))
      (node (ref "D15") (pin "C") (pinfunction "C_C") (pintype "passive"))
      (node (ref "D3") (pin "C") (pinfunction "C_C") (pintype "passive"))
      (node (ref "D7") (pin "C") (pinfunction "C_C") (pintype "passive"))
      (node (ref "IC1") (pin "79") (pinfunction "PC11_79") (pintype "bidirectional"))
    )
    (net (code "101") (name "SWITCH_OUT4") (class "Default")
      (node (ref "D12") (pin "C") (pinfunction "C_C") (pintype "passive"))
      (node (ref "D16") (pin "C") (pinfunction "C_C") (pintype "passive"))
      (node (ref "D4") (pin "C") (pinfunction "C_C") (pintype "passive"))
      (node (ref "D8") (pin "C") (pinfunction "C_C") (pintype "passive"))
      (node (ref "IC1") (pin "78") (pinfunction "PC10_78") (pintype "bidirectional"))
    )
    (net (code "102") (name "SWITCH_OUT5") (class "Default")
      (node (ref "D13") (pin "C") (pinfunction "C_C") (pintype "passive"))
      (node (ref "D17") (pin "C") (pinfunction "C_C") (pintype "passive"))
      (node (ref "D18") (pin "C") (pinfunction "C_C") (pintype "passive"))
      (node (ref "D19") (pin "C") (pinfunction "C_C") (pintype "passive"))
      (node (ref "IC1") (pin "64") (pinfunction "PC7_64") (pintype "bidirectional"))
    )
    (net (code "103") (name "SWITCH_OUT6") (class "Default")
      (node (ref "D20") (pin "C") (pinfunction "C_C") (pintype "passive"))
      (node (ref "D21") (pin "C") (pinfunction "C_C") (pintype "passive"))
      (node (ref "D22") (pin "C") (pinfunction "C_C") (pintype "passive"))
      (node (ref "IC1") (pin "36") (pinfunction "PB1_36") (pintype "bidirectional"))
    )
    (net (code "104") (name "USB_N") (class "Default")
      (node (ref "IC1") (pin "70") (pinfunction "PA11_70") (pintype "bidirectional"))
      (node (ref "R2") (pin "1") (pinfunction "1_1") (pintype "passive"))
    )
    (net (code "105") (name "USB_P") (class "Default")
      (node (ref "IC1") (pin "71") (pinfunction "PA12_71") (pintype "bidirectional"))
      (node (ref "R3") (pin "1") (pinfunction "1_1") (pintype "passive"))
    )
    (net (code "106") (name "USB_PULLUP") (class "Default")
      (node (ref "IC1") (pin "3") (pinfunction "PE4_3") (pintype "bidirectional"))
      (node (ref "R6") (pin "2") (pinfunction "2_2") (pintype "passive"))
    )
    (net (code "107") (name "WR") (class "Default")
      (node (ref "DISPLAY1") (pin "9") (pinfunction "WR_9") (pintype "bidirectional"))
      (node (ref "IC1") (pin "54") (pinfunction "PB15_54") (pintype "bidirectional"))
    )
    (net (code "108") (name "unconnected-(1-P-Pad3)") (class "Default")
      (node (ref "1") (pin "3") (pinfunction "P_3") (pintype "passive"))
    )
    (net (code "109") (name "unconnected-(1-S1-Pad2)") (class "Default")
      (node (ref "1") (pin "2") (pinfunction "S1_2") (pintype "passive"))
    )
    (net (code "110") (name "unconnected-(2-P-Pad3)") (class "Default")
      (node (ref "2") (pin "3") (pinfunction "P_3") (pintype "passive"))
    )
    (net (code "111") (name "unconnected-(3-P-Pad3)") (class "Default")
      (node (ref "3") (pin "3") (pinfunction "P_3") (pintype "passive"))
    )
    (net (code "112") (name "unconnected-(4-P-Pad3)") (class "Default")
      (node (ref "4") (pin "3") (pinfunction "P_3") (pintype "passive"))
    )
    (net (code "113") (name "unconnected-(5-P-Pad3)") (class "Default")
      (node (ref "5") (pin "3") (pinfunction "P_3") (pintype "passive"))
    )
    (net (code "114") (name "unconnected-(5-S1-Pad2)") (class "Default")
      (node (ref "5") (pin "2") (pinfunction "S1_2") (pintype "passive"))
    )
    (net (code "115") (name "unconnected-(6-P-Pad3)") (class "Default")
      (node (ref "6") (pin "3") (pinfunction "P_3") (pintype "passive"))
    )
    (net (code "116") (name "unconnected-(7-P-Pad3)") (class "Default")
      (node (ref "7") (pin "3") (pinfunction "P_3") (pintype "passive"))
    )
    (net (code "117") (name "unconnected-(8-P-Pad3)") (class "Default")
      (node (ref "8") (pin "3") (pinfunction "P_3") (pintype "passive"))
    )
    (net (code "118") (name "unconnected-(9-P-Pad3)") (class "Default")
      (node (ref "9") (pin "3") (pinfunction "P_3") (pintype "passive"))
    )
    (net (code "119") (name "unconnected-(9-S1-Pad2)") (class "Default")
      (node (ref "9") (pin "2") (pinfunction "S1_2") (pintype "passive"))
    )
    (net (code "120") (name "unconnected-(10-P-Pad3)") (class "Default")
      (node (ref "10") (pin "3") (pinfunction "P_3") (pintype "passive"))
    )
    (net (code "121") (name "unconnected-(11-P-Pad3)") (class "Default")
      (node (ref "11") (pin "3") (pinfunction "P_3") (pintype "passive"))
    )
    (net (code "122") (name "unconnected-(12-P-Pad3)") (class "Default")
      (node (ref "12") (pin "3") (pinfunction "P_3") (pintype "passive"))
    )
    (net (code "123") (name "unconnected-(13-P-Pad3)") (class "Default")
      (node (ref "13") (pin "3") (pinfunction "P_3") (pintype "passive"))
    )
    (net (code "124") (name "unconnected-(14-P-Pad3)") (class "Default")
      (node (ref "14") (pin "3") (pinfunction "P_3") (pintype "passive"))
    )
    (net (code "125") (name "unconnected-(15-P-Pad3)") (class "Default")
      (node (ref "15") (pin "3") (pinfunction "P_3") (pintype "passive"))
    )
    (net (code "126") (name "unconnected-(16-P-Pad3)") (class "Default")
      (node (ref "16") (pin "3") (pinfunction "P_3") (pintype "passive"))
    )
    (net (code "127") (name "unconnected-(17-P-Pad3)") (class "Default")
      (node (ref "17") (pin "3") (pinfunction "P_3") (pintype "passive"))
    )
    (net (code "128") (name "unconnected-(18-P-Pad3)") (class "Default")
      (node (ref "18") (pin "3") (pinfunction "P_3") (pintype "passive"))
    )
    (net (code "129") (name "unconnected-(18-S-Pad1)") (class "Default")
      (node (ref "18") (pin "1") (pinfunction "S_1") (pintype "passive"))
    )
    (net (code "130") (name "unconnected-(19-P-Pad3)") (class "Default")
      (node (ref "19") (pin "3") (pinfunction "P_3") (pintype "passive"))
    )
    (net (code "131") (name "unconnected-(19-S-Pad1)") (class "Default")
      (node (ref "19") (pin "1") (pinfunction "S_1") (pintype "passive"))
    )
    (net (code "132") (name "unconnected-(20-P-Pad3)") (class "Default")
      (node (ref "20") (pin "3") (pinfunction "P_3") (pintype "passive"))
    )
    (net (code "133") (name "unconnected-(20-S-Pad1)") (class "Default")
      (node (ref "20") (pin "1") (pinfunction "S_1") (pintype "passive"))
    )
    (net (code "134") (name "unconnected-(21-P-Pad3)") (class "Default")
      (node (ref "21") (pin "3") (pinfunction "P_3") (pintype "passive"))
    )
    (net (code "135") (name "unconnected-(21-S-Pad1)") (class "Default")
      (node (ref "21") (pin "1") (pinfunction "S_1") (pintype "passive"))
    )
    (net (code "136") (name "unconnected-(DISPLAY1A-BUSY-Pad24)") (class "Default")
      (node (ref "DISPLAY1") (pin "24") (pinfunction "BUSY_24") (pintype "bidirectional"))
    )
    (net (code "137") (name "unconnected-(IC1A-PB2-Pad37)") (class "Default")
      (node (ref "IC1") (pin "37") (pinfunction "PB2_37") (pintype "bidirectional"))
    )
    (net (code "138") (name "unconnected-(IC1A-PB10-Pad47)") (class "Default")
      (node (ref "IC1") (pin "47") (pinfunction "PB10_47") (pintype "bidirectional"))
    )
    (net (code "139") (name "unconnected-(IC1A-PB11-Pad48)") (class "Default")
      (node (ref "IC1") (pin "48") (pinfunction "PB11_48") (pintype "bidirectional"))
    )
    (net (code "140") (name "unconnected-(IC1A-PB12-Pad51)") (class "Default")
      (node (ref "IC1") (pin "51") (pinfunction "PB12_51") (pintype "bidirectional"))
    )
    (net (code "141") (name "unconnected-(IC1A-PB13-Pad52)") (class "Default")
      (node (ref "IC1") (pin "52") (pinfunction "PB13_52") (pintype "bidirectional"))
    )
    (net (code "142") (name "unconnected-(IC1A-PC4-Pad33)") (class "Default")
      (node (ref "IC1") (pin "33") (pinfunction "PC4_33") (pintype "bidirectional"))
    )
    (net (code "143") (name "unconnected-(IC1A-PC5-Pad34)") (class "Default")
      (node (ref "IC1") (pin "34") (pinfunction "PC5_34") (pintype "bidirectional"))
    )
    (net (code "144") (name "unconnected-(IC1A-PC8-Pad65)") (class "Default")
      (node (ref "IC1") (pin "65") (pinfunction "PC8_65") (pintype "bidirectional"))
    )
    (net (code "145") (name "unconnected-(IC1A-PC13-Pad7)") (class "Default")
      (node (ref "IC1") (pin "7") (pinfunction "PC13_7") (pintype "bidirectional"))
    )
    (net (code "146") (name "unconnected-(IC1A-PC15-Pad9)") (class "Default")
      (node (ref "IC1") (pin "9") (pinfunction "PC15_9") (pintype "bidirectional"))
    )
    (net (code "147") (name "unconnected-(IC1A-PE5-Pad4)") (class "Default")
      (node (ref "IC1") (pin "4") (pinfunction "PE5_4") (pintype "bidirectional"))
    )
    (net (code "148") (name "unconnected-(IC1A-PE6-Pad5)") (class "Default")
      (node (ref "IC1") (pin "5") (pinfunction "PE6_5") (pintype "bidirectional"))
    )
    (net (code "149") (name "unconnected-(IC1A-PE7-Pad38)") (class "Default")
      (node (ref "IC1") (pin "38") (pinfunction "PE7_38") (pintype "bidirectional"))
    )
    (net (code "150") (name "unconnected-(IC1A-PE8-Pad39)") (class "Default")
      (node (ref "IC1") (pin "39") (pinfunction "PE8_39") (pintype "bidirectional"))
    )
    (net (code "151") (name "unconnected-(IC1A-PE9-Pad40)") (class "Default")
      (node (ref "IC1") (pin "40") (pinfunction "PE9_40") (pintype "bidirectional"))
    )
    (net (code "152") (name "unconnected-(IC1A-PE10-Pad41)") (class "Default")
      (node (ref "IC1") (pin "41") (pinfunction "PE10_41") (pintype "bidirectional"))
    )
    (net (code "153") (name "unconnected-(IC1A-PE11-Pad42)") (class "Default")
      (node (ref "IC1") (pin "42") (pinfunction "PE11_42") (pintype "bidirectional"))
    )
    (net (code "154") (name "unconnected-(IC1A-PE12-Pad43)") (class "Default")
      (node (ref "IC1") (pin "43") (pinfunction "PE12_43") (pintype "bidirectional"))
    )
    (net (code "155") (name "unconnected-(IC1A-PE13-Pad44)") (class "Default")
      (node (ref "IC1") (pin "44") (pinfunction "PE13_44") (pintype "bidirectional"))
    )
    (net (code "156") (name "unconnected-(IC1A-PE14-Pad45)") (class "Default")
      (node (ref "IC1") (pin "45") (pinfunction "PE14_45") (pintype "bidirectional"))
    )
    (net (code "157") (name "unconnected-(IC1A-PE15-Pad46)") (class "Default")
      (node (ref "IC1") (pin "46") (pinfunction "PE15_46") (pintype "bidirectional"))
    )
    (net (code "158") (name "unconnected-(X1-Pad1)") (class "Default")
      (node (ref "X1") (pin "1") (pinfunction "1_1") (pintype "passive"))
    )
  )
)
